# design.net
KiCad netlist of a schematic drawn in Altium Designer
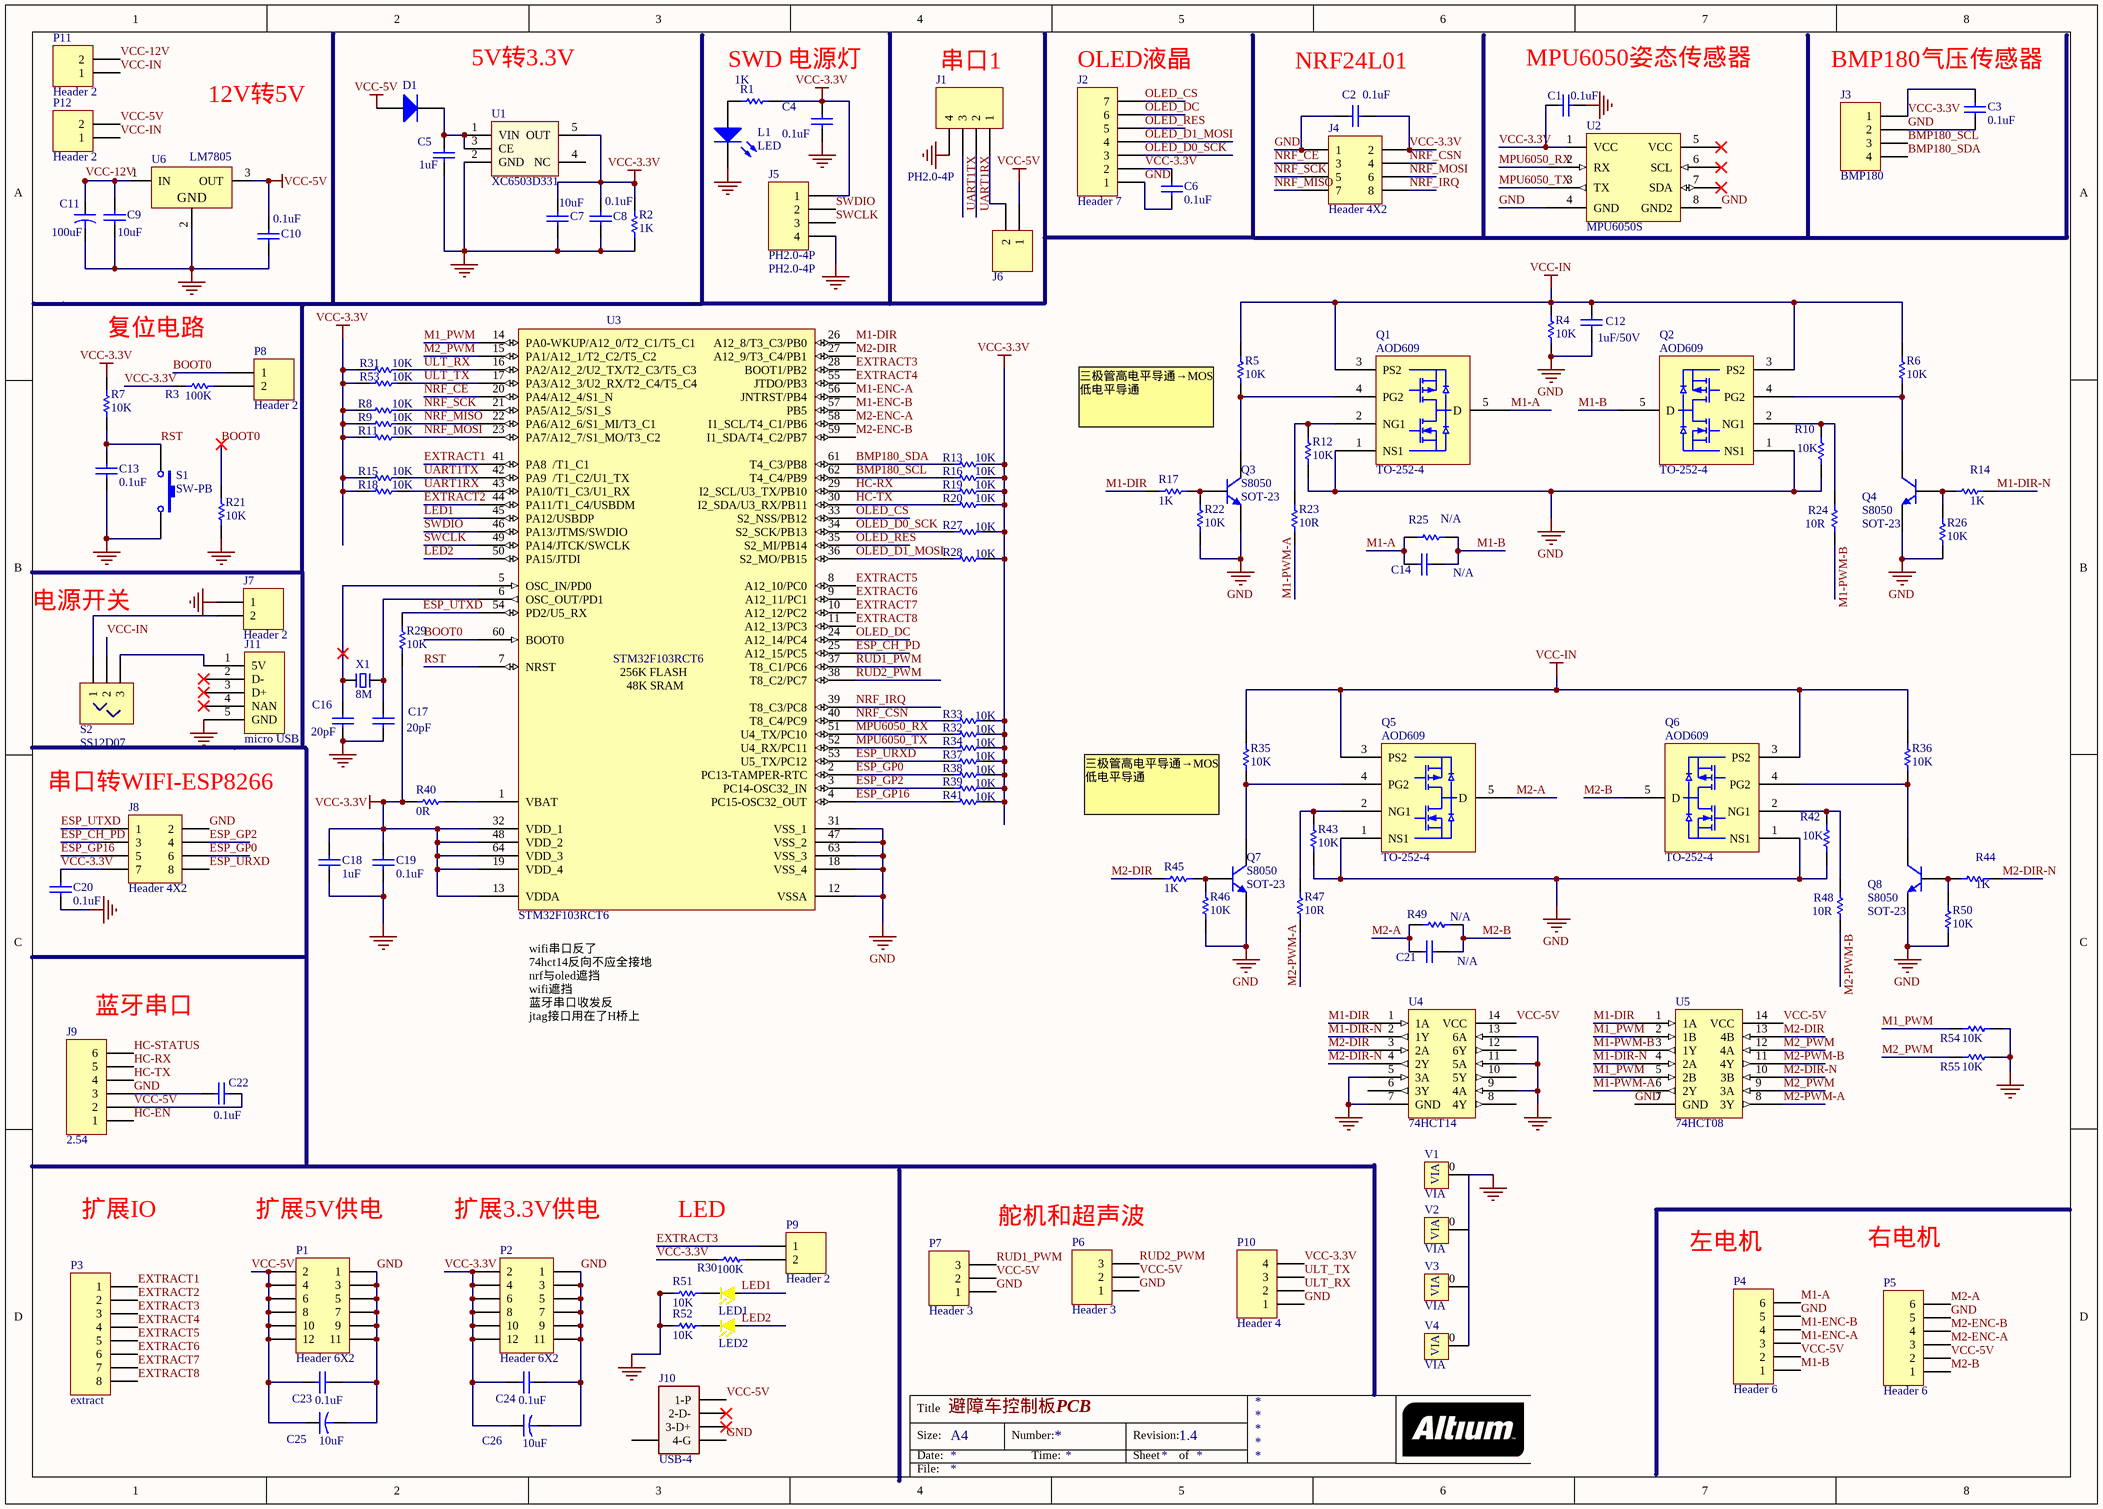
[diagram p0: 避障车控制板.SchDoc]

(export (version "E")
  (design (tool "Eeschema 10.0.6"))
  (components
    (comp (ref "C1")
      (value "0.1uF")
      (footprint "0805_N_LY")
      (description "Capacitor")
      (fields (field (name "PUBLISHER") "Altium Limited"))
      (libsource (lib "Miscellaneous Devices") (part "Cap"))
    )
    (comp (ref "C2")
      (value "0.1uF")
      (footprint "0805_N_LY")
      (description "Capacitor")
      (fields (field (name "PUBLISHER") "Altium Limited"))
      (libsource (lib "Miscellaneous Devices") (part "Cap"))
    )
    (comp (ref "C3")
      (value "0.1uF")
      (footprint "0805_N_LY")
      (description "电容0603")
      (fields (field (name "PUBLISHER") "Altium Limited"))
      (libsource (lib "Liyao原理图库") (part "Cap"))
    )
    (comp (ref "C4")
      (value "0.1uF")
      (footprint "0805_N_LY")
      (description "Capacitor")
      (fields (field (name "PUBLISHER") "Altium Limited"))
      (libsource (lib "Miscellaneous Devices") (part "Cap"))
    )
    (comp (ref "C5")
      (value "1uF")
      (footprint "0805_N_LY")
      (description "Capacitor")
      (fields (field (name "PUBLISHER") "Altium Limited"))
      (libsource (lib "Miscellaneous Devices") (part "Cap"))
    )
    (comp (ref "C6")
      (value "0.1uF")
      (footprint "0805_N_LY")
      (description "Capacitor")
      (fields (field (name "PUBLISHER") "Altium Limited"))
      (libsource (lib "Miscellaneous Devices") (part "Cap"))
    )
    (comp (ref "C7")
      (value "10uF")
      (footprint "0805_N_LY")
      (description "Capacitor")
      (fields (field (name "PUBLISHER") "Altium Limited"))
      (libsource (lib "Miscellaneous Devices") (part "Cap"))
    )
    (comp (ref "C8")
      (value "0.1uF")
      (footprint "0805_N_LY")
      (description "Capacitor")
      (fields (field (name "PUBLISHER") "Altium Limited"))
      (libsource (lib "Miscellaneous Devices") (part "Cap"))
    )
    (comp (ref "C9")
      (value "10uF")
      (footprint "0805_N_LY")
      (description "Capacitor")
      (fields (field (name "PUBLISHER") "Altium Limited"))
      (libsource (lib "Miscellaneous Devices") (part "Cap"))
    )
    (comp (ref "C10")
      (value "0.1uF")
      (footprint "0805_N_LY")
      (description "Capacitor")
      (fields (field (name "PUBLISHER") "Altium Limited"))
      (libsource (lib "Miscellaneous Devices") (part "Cap"))
    )
    (comp (ref "C11")
      (value "100uF")
      (footprint "TC6.3*7.7")
      (description "100uf/35v电解电容")
      (fields (field (name "PUBLISHER") "Altium Limited"))
      (libsource (lib "Liyao原理图库") (part "Cap100uf"))
    )
    (comp (ref "C12")
      (value "1uF/50V")
      (footprint "0805_N_LY")
      (description "Capacitor")
      (fields (field (name "PUBLISHER") "Altium Limited"))
      (libsource (lib "Miscellaneous Devices") (part "Cap"))
    )
    (comp (ref "C13")
      (value "0.1uF")
      (footprint "0805_N_LY")
      (description "Capacitor")
      (fields (field (name "PUBLISHER") "Altium Limited"))
      (libsource (lib "Miscellaneous Devices") (part "Cap"))
    )
    (comp (ref "C14")
      (value "N/A")
      (footprint "0805_N_LY")
      (description "Capacitor")
      (fields (field (name "PUBLISHER") "Altium Limited"))
      (libsource (lib "Miscellaneous Devices") (part "Cap"))
    )
    (comp (ref "C16")
      (value "20pF")
      (footprint "0805_N_LY")
      (description "Capacitor")
      (fields (field (name "PUBLISHER") "Altium Limited"))
      (libsource (lib "Miscellaneous Devices") (part "Cap"))
    )
    (comp (ref "C17")
      (value "20pF")
      (footprint "0805_N_LY")
      (description "Capacitor")
      (fields (field (name "PUBLISHER") "Altium Limited"))
      (libsource (lib "Miscellaneous Devices") (part "Cap"))
    )
    (comp (ref "C18")
      (value "1uF")
      (footprint "0805_N_LY")
      (description "Capacitor")
      (fields (field (name "PUBLISHER") "Altium Limited"))
      (libsource (lib "Miscellaneous Devices") (part "Cap"))
    )
    (comp (ref "C19")
      (value "0.1uF")
      (footprint "0805_N_LY")
      (description "Capacitor")
      (fields (field (name "PUBLISHER") "Altium Limited"))
      (libsource (lib "Miscellaneous Devices") (part "Cap"))
    )
    (comp (ref "C20")
      (value "0.1uF")
      (footprint "0805_N_LY")
      (description "Capacitor")
      (fields (field (name "PUBLISHER") "Altium Limited"))
      (libsource (lib "Miscellaneous Devices") (part "Cap"))
    )
    (comp (ref "C21")
      (value "N/A")
      (footprint "0805_N_LY")
      (description "Capacitor")
      (fields (field (name "PUBLISHER") "Altium Limited"))
      (libsource (lib "Miscellaneous Devices") (part "Cap"))
    )
    (comp (ref "C22")
      (value "0.1uF")
      (footprint "0805_N_LY")
      (description "Capacitor")
      (fields (field (name "PUBLISHER") "Altium Limited"))
      (libsource (lib "Miscellaneous Devices") (part "Cap"))
    )
    (comp (ref "C23")
      (value "0.1uF")
      (footprint "0805_N_LY")
      (description "电容0603")
      (fields (field (name "PUBLISHER") "Altium Limited"))
      (libsource (lib "Liyao原理图库") (part "Cap"))
    )
    (comp (ref "C24")
      (value "0.1uF")
      (footprint "0805_N_LY")
      (description "电容0603")
      (fields (field (name "PUBLISHER") "Altium Limited"))
      (libsource (lib "Liyao原理图库") (part "Cap"))
    )
    (comp (ref "C25")
      (value "10uF")
      (footprint "TC5*5")
      (description "10uf/35v电解电容")
      (fields (field (name "PUBLISHER") "Altium Limited"))
      (libsource (lib "Liyao原理图库") (part "Cap10uf"))
    )
    (comp (ref "C26")
      (value "10uF")
      (footprint "TC5*5")
      (description "10uf/35v电解电容")
      (fields (field (name "PUBLISHER") "Altium Limited"))
      (libsource (lib "Liyao原理图库") (part "Cap10uf"))
    )
    (comp (ref "D1")
      (value "SS14")
      (footprint "SMA")
      (description "28V 1A")
      (fields (field (name "PUBLISHER") "Altium Limited"))
      (libsource (lib "Liyao原理图库") (part "SS14"))
    )
    (comp (ref "J1")
      (value "PH2.0-4P")
      (footprint "XH2.54-4P")
      (description "插座XH2.54-4P")
      (fields (field (name "Comment") "XH2.54-4P") (field (name "PUBLISHER") "Altium Limited"))
      (libsource (lib "Liyao原理图库") (part "XH2.54-4P"))
    )
    (comp (ref "J2")
      (value "Header 7")
      (footprint "HDR1X7")
      (description "Header, 7-Pin")
      (fields (field (name "PUBLISHER") "Altium Limited"))
      (libsource (lib "Miscellaneous Connectors") (part "Header 7"))
    )
    (comp (ref "J3")
      (value "BMP180")
      (footprint "HDR1X4")
      (description "Header, 4-Pin")
      (fields (field (name "Comment") "PH2.0-4P") (field (name "PUBLISHER") "Altium Limited"))
      (libsource (lib "") (part "Header 4_1"))
    )
    (comp (ref "J4")
      (value "Header 4X2")
      (footprint "HDR2X4")
      (description "Header, 4-Pin, Dual row")
      (fields (field (name "PUBLISHER") "Altium Limited"))
      (libsource (lib "Miscellaneous Connectors") (part "Header 4X2"))
    )
    (comp (ref "J5")
      (value "PH2.0-4P")
      (footprint "PH2.0-4P")
      (description "Header, 4-Pin")
      (fields (field (name "ALTIUM_VALUE") "PH2.0-4P") (field (name "PUBLISHER") "Altium Limited"))
      (libsource (lib "") (part "Header 4_1"))
    )
    (comp (ref "J6")
      (value "XH2.54-2P")
      (footprint "CAP2.54-2P")
      (description "插座XH2.54-2P")
      (fields (field (name "PUBLISHER") "Altium Limited"))
      (libsource (lib "Liyao原理图库") (part "XH2.54-2P"))
    )
    (comp (ref "J7")
      (value "Header 2")
      (footprint "XH2.54-2P")
      (description "Header, 2-Pin")
      (fields (field (name "PUBLISHER") "Altium Limited"))
      (libsource (lib "Miscellaneous Connectors") (part "Header 2"))
    )
    (comp (ref "J8")
      (value "Header 4X2")
      (footprint "HDR2X4")
      (description "Header, 4-Pin, Dual row")
      (fields (field (name "PUBLISHER") "Altium Limited"))
      (libsource (lib "Miscellaneous Connectors") (part "Header 4X2"))
    )
    (comp (ref "J9")
      (value "2.54")
      (footprint "HDR1X6")
      (description "Header, 6-Pin")
      (fields (field (name "PUBLISHER") "Altium Limited"))
      (libsource (lib "Liyao端子库") (part "Header 6"))
    )
    (comp (ref "J10") (value "USB-4") (footprint "USB-C") (libsource (lib "Liyao原理图库") (part "USB_B")))
    (comp (ref "J11")
      (value "micro USB")
      (footprint "MICRO-USB")
      (description "micro USB母")
      (libsource (lib "Liyao原理图库") (part "micro USB"))
    )
    (comp (ref "L1") (value "LED") (footprint "0805_N_LED_LY") (libsource (lib "Sparks") (part "LED")))
    (comp (ref "LED1")
      (value "LED-Y")
      (footprint "0805_N_LED_LY")
      (description "LED黄0603")
      (libsource (lib "Liyao原理图库") (part "LED-Y"))
    )
    (comp (ref "LED2")
      (value "LED-Y")
      (footprint "0805_N_LED_LY")
      (description "LED黄0603")
      (libsource (lib "Liyao原理图库") (part "LED-Y"))
    )
    (comp (ref "P1")
      (value "Header 6X2")
      (footprint "HDR2X6")
      (description "Header, 6-Pin, Dual row")
      (fields (field (name "PUBLISHER") "Altium Limited"))
      (libsource (lib "Miscellaneous Connectors") (part "Header 6X2"))
    )
    (comp (ref "P2")
      (value "Header 6X2")
      (footprint "HDR2X6")
      (description "Header, 6-Pin, Dual row")
      (fields (field (name "PUBLISHER") "Altium Limited"))
      (libsource (lib "Miscellaneous Connectors") (part "Header 6X2"))
    )
    (comp (ref "P3")
      (value "extract")
      (footprint "HDR1X8")
      (description "Header, 8-Pin")
      (fields (field (name "PUBLISHER") "Altium Limited"))
      (libsource (lib "Miscellaneous Connectors") (part "Header 8"))
    )
    (comp (ref "P4")
      (value "Header 6")
      (footprint "PH2.0-6p")
      (description "Header, 6-Pin")
      (fields (field (name "PUBLISHER") "Altium Limited"))
      (libsource (lib "Miscellaneous Connectors") (part "Header 6"))
    )
    (comp (ref "P5")
      (value "Header 6")
      (footprint "PH2.0-6p")
      (description "Header, 6-Pin")
      (fields (field (name "PUBLISHER") "Altium Limited"))
      (libsource (lib "Miscellaneous Connectors") (part "Header 6"))
    )
    (comp (ref "P6")
      (value "Header 3")
      (footprint "HDR1X3")
      (description "Header, 3-Pin")
      (fields (field (name "PUBLISHER") "Altium Limited"))
      (libsource (lib "Miscellaneous Connectors") (part "Header 3"))
    )
    (comp (ref "P7")
      (value "Header 3")
      (footprint "HDR1X3")
      (description "Header, 3-Pin")
      (fields (field (name "PUBLISHER") "Altium Limited"))
      (libsource (lib "Miscellaneous Connectors") (part "Header 3"))
    )
    (comp (ref "P8")
      (value "Header 2")
      (footprint "HDR1X2")
      (description "Header, 2-Pin")
      (fields (field (name "PUBLISHER") "Altium Limited"))
      (libsource (lib "Liyao端子库") (part "Header 2"))
    )
    (comp (ref "P9")
      (value "Header 2")
      (footprint "HDR1X2")
      (description "Header, 2-Pin")
      (fields (field (name "PUBLISHER") "Altium Limited"))
      (libsource (lib "Liyao端子库") (part "Header 2"))
    )
    (comp (ref "P10")
      (value "Header 4")
      (footprint "HDR1X4")
      (description "Header, 4-Pin")
      (fields (field (name "PUBLISHER") "Altium Limited"))
      (libsource (lib "Miscellaneous Connectors") (part "Header 4"))
    )
    (comp (ref "P11")
      (value "Header 2")
      (footprint "CAP2.54-2P")
      (description "Header, 2-Pin")
      (fields (field (name "PUBLISHER") "Altium Limited"))
      (libsource (lib "") (part "Header 2_1"))
    )
    (comp (ref "P12")
      (value "Header 2")
      (footprint "CAP2.54-2P")
      (description "Header, 2-Pin")
      (fields (field (name "PUBLISHER") "Altium Limited"))
      (libsource (lib "") (part "Header 2_1"))
    )
    (comp (ref "Q1")
      (value "TO-252-4")
      (footprint "TO-252-4L")
      (fields (field (name "ALTIUM_VALUE") "AOD609"))
      (libsource (lib "") (part "MOS-DUAL-N/P_1"))
    )
    (comp (ref "Q2")
      (value "TO-252-4")
      (footprint "TO-252-4L")
      (fields (field (name "ALTIUM_VALUE") "AOD609"))
      (libsource (lib "CYSchlib") (part "MOS-DUAL-N/P"))
    )
    (comp (ref "Q3")
      (value "SOT-23")
      (footprint "SOT-23_N_LY")
      (description "NPN Bipolar Transistor")
      (fields (field (name "ALTIUM_VALUE") "S8050") (field (name "PUBLISHER") "Altium Limited"))
      (libsource (lib "CYSchlib") (part "NPN"))
    )
    (comp (ref "Q4")
      (value "SOT-23")
      (footprint "SOT-23_N_LY")
      (description "NPN Bipolar Transistor")
      (fields (field (name "ALTIUM_VALUE") "S8050") (field (name "PUBLISHER") "Altium Limited"))
      (libsource (lib "CYSchlib") (part "NPN"))
    )
    (comp (ref "Q5")
      (value "TO-252-4")
      (footprint "TO-252-4L")
      (fields (field (name "ALTIUM_VALUE") "AOD609"))
      (libsource (lib "") (part "MOS-DUAL-N/P_1"))
    )
    (comp (ref "Q6")
      (value "TO-252-4")
      (footprint "TO-252-4L")
      (fields (field (name "ALTIUM_VALUE") "AOD609"))
      (libsource (lib "CYSchlib") (part "MOS-DUAL-N/P"))
    )
    (comp (ref "Q7")
      (value "SOT-23")
      (footprint "SOT-23_N_LY")
      (description "NPN Bipolar Transistor")
      (fields (field (name "ALTIUM_VALUE") "S8050") (field (name "PUBLISHER") "Altium Limited"))
      (libsource (lib "CYSchlib") (part "NPN"))
    )
    (comp (ref "Q8")
      (value "SOT-23")
      (footprint "SOT-23_N_LY")
      (description "NPN Bipolar Transistor")
      (fields (field (name "ALTIUM_VALUE") "S8050") (field (name "PUBLISHER") "Altium Limited"))
      (libsource (lib "CYSchlib") (part "NPN"))
    )
    (comp (ref "R1")
      (value "1K")
      (footprint "0805_N_LY")
      (description "Resistor")
      (fields (field (name "PUBLISHER") "Altium Limited"))
      (libsource (lib "Miscellaneous Devices") (part "Res1"))
    )
    (comp (ref "R2")
      (value "1K")
      (footprint "0805_N_LY")
      (description "Resistor")
      (fields (field (name "PUBLISHER") "Altium Limited"))
      (libsource (lib "Miscellaneous Devices") (part "Res1"))
    )
    (comp (ref "R3")
      (value "100K")
      (footprint "0805_N_LY")
      (description "电阻0603")
      (fields (field (name "PUBLISHER") "Altium Limited"))
      (libsource (lib "Liyao原理图库") (part "Res"))
    )
    (comp (ref "R4")
      (value "10K")
      (footprint "0805_N_LY")
      (description "Resistor")
      (fields (field (name "PUBLISHER") "Altium Limited"))
      (libsource (lib "Miscellaneous Devices") (part "Res1"))
    )
    (comp (ref "R5")
      (value "10K")
      (footprint "0805_N_LY")
      (description "Resistor")
      (fields (field (name "PUBLISHER") "Altium Limited"))
      (libsource (lib "Miscellaneous Devices") (part "Res1"))
    )
    (comp (ref "R6")
      (value "10K")
      (footprint "0805_N_LY")
      (description "Resistor")
      (fields (field (name "PUBLISHER") "Altium Limited"))
      (libsource (lib "Miscellaneous Devices") (part "Res1"))
    )
    (comp (ref "R7")
      (value "10K")
      (footprint "0805_N_LY")
      (description "Resistor")
      (fields (field (name "PUBLISHER") "Altium Limited"))
      (libsource (lib "Miscellaneous Devices") (part "Res1"))
    )
    (comp (ref "R8")
      (value "10K")
      (footprint "0805_N_LY")
      (description "电阻0603")
      (fields (field (name "PUBLISHER") "Altium Limited"))
      (libsource (lib "Liyao原理图库") (part "Res"))
    )
    (comp (ref "R9")
      (value "10K")
      (footprint "0805_N_LY")
      (description "电阻0603")
      (fields (field (name "PUBLISHER") "Altium Limited"))
      (libsource (lib "Liyao原理图库") (part "Res"))
    )
    (comp (ref "R10")
      (value "10K")
      (footprint "0805_N_LY")
      (description "Resistor")
      (fields (field (name "PUBLISHER") "Altium Limited"))
      (libsource (lib "Miscellaneous Devices") (part "Res1"))
    )
    (comp (ref "R11")
      (value "10K")
      (footprint "0805_N_LY")
      (description "电阻0603")
      (fields (field (name "PUBLISHER") "Altium Limited"))
      (libsource (lib "Liyao原理图库") (part "Res"))
    )
    (comp (ref "R12")
      (value "10K")
      (footprint "0805_N_LY")
      (description "Resistor")
      (fields (field (name "PUBLISHER") "Altium Limited"))
      (libsource (lib "Miscellaneous Devices") (part "Res1"))
    )
    (comp (ref "R13")
      (value "10K")
      (footprint "0805_N_LY")
      (description "电阻0603")
      (fields (field (name "PUBLISHER") "Altium Limited"))
      (libsource (lib "Liyao原理图库") (part "Res"))
    )
    (comp (ref "R14")
      (value "1K")
      (footprint "0805_N_LY")
      (description "Resistor")
      (fields (field (name "PUBLISHER") "Altium Limited"))
      (libsource (lib "Miscellaneous Devices") (part "Res1"))
    )
    (comp (ref "R15")
      (value "10K")
      (footprint "0805_N_LY")
      (description "电阻0603")
      (fields (field (name "PUBLISHER") "Altium Limited"))
      (libsource (lib "Liyao原理图库") (part "Res"))
    )
    (comp (ref "R16")
      (value "10K")
      (footprint "0805_N_LY")
      (description "电阻0603")
      (fields (field (name "PUBLISHER") "Altium Limited"))
      (libsource (lib "Liyao原理图库") (part "Res"))
    )
    (comp (ref "R17")
      (value "1K")
      (footprint "0805_N_LY")
      (description "Resistor")
      (fields (field (name "PUBLISHER") "Altium Limited"))
      (libsource (lib "Miscellaneous Devices") (part "Res1"))
    )
    (comp (ref "R18")
      (value "10K")
      (footprint "0805_N_LY")
      (description "电阻0603")
      (fields (field (name "PUBLISHER") "Altium Limited"))
      (libsource (lib "Liyao原理图库") (part "Res"))
    )
    (comp (ref "R19")
      (value "10K")
      (footprint "0805_N_LY")
      (description "电阻0603")
      (fields (field (name "PUBLISHER") "Altium Limited"))
      (libsource (lib "Liyao原理图库") (part "Res"))
    )
    (comp (ref "R20")
      (value "10K")
      (footprint "0805_N_LY")
      (description "电阻0603")
      (fields (field (name "PUBLISHER") "Altium Limited"))
      (libsource (lib "Liyao原理图库") (part "Res"))
    )
    (comp (ref "R21")
      (value "10K")
      (footprint "0805_N_LY")
      (description "Resistor")
      (fields (field (name "PUBLISHER") "Altium Limited"))
      (libsource (lib "Miscellaneous Devices") (part "Res1"))
    )
    (comp (ref "R22")
      (value "10K")
      (footprint "0805_N_LY")
      (description "Resistor")
      (fields (field (name "PUBLISHER") "Altium Limited"))
      (libsource (lib "Miscellaneous Devices") (part "Res1"))
    )
    (comp (ref "R23")
      (value "10R")
      (footprint "0805_N_LY")
      (description "Resistor")
      (fields (field (name "PUBLISHER") "Altium Limited"))
      (libsource (lib "Miscellaneous Devices") (part "Res1"))
    )
    (comp (ref "R24")
      (value "10R")
      (footprint "0805_N_LY")
      (description "Resistor")
      (fields (field (name "PUBLISHER") "Altium Limited"))
      (libsource (lib "Miscellaneous Devices") (part "Res1"))
    )
    (comp (ref "R25")
      (value "N/A")
      (footprint "0805_N_LY")
      (description "Resistor")
      (fields (field (name "PUBLISHER") "Altium Limited"))
      (libsource (lib "Miscellaneous Devices") (part "Res1"))
    )
    (comp (ref "R26")
      (value "10K")
      (footprint "0805_N_LY")
      (description "Resistor")
      (fields (field (name "PUBLISHER") "Altium Limited"))
      (libsource (lib "Miscellaneous Devices") (part "Res1"))
    )
    (comp (ref "R27")
      (value "10K")
      (footprint "0805_N_LY")
      (description "电阻0603")
      (fields (field (name "PUBLISHER") "Altium Limited"))
      (libsource (lib "Liyao原理图库") (part "Res"))
    )
    (comp (ref "R28")
      (value "10K")
      (footprint "0805_N_LY")
      (description "电阻0603")
      (fields (field (name "PUBLISHER") "Altium Limited"))
      (libsource (lib "Liyao原理图库") (part "Res"))
    )
    (comp (ref "R29")
      (value "10K")
      (footprint "0805_N_LY")
      (description "电阻0603")
      (fields (field (name "PUBLISHER") "Altium Limited"))
      (libsource (lib "Liyao原理图库") (part "Res"))
    )
    (comp (ref "R30")
      (value "100K")
      (footprint "0805_N_LY")
      (description "电阻0603")
      (fields (field (name "PUBLISHER") "Altium Limited"))
      (libsource (lib "Liyao原理图库") (part "Res"))
    )
    (comp (ref "R31")
      (value "10K")
      (footprint "0805_N_LY")
      (description "电阻")
      (fields (field (name "PUBLISHER") "Altium Limited"))
      (libsource (lib "Liyao原理图库") (part "Res"))
    )
    (comp (ref "R32")
      (value "10K")
      (footprint "0805_N_LY")
      (description "电阻0603")
      (fields (field (name "PUBLISHER") "Altium Limited"))
      (libsource (lib "Liyao原理图库") (part "Res"))
    )
    (comp (ref "R33")
      (value "10K")
      (footprint "0805_N_LY")
      (description "电阻0603")
      (fields (field (name "PUBLISHER") "Altium Limited"))
      (libsource (lib "Liyao原理图库") (part "Res"))
    )
    (comp (ref "R34")
      (value "10K")
      (footprint "0805_N_LY")
      (description "电阻0603")
      (fields (field (name "PUBLISHER") "Altium Limited"))
      (libsource (lib "Liyao原理图库") (part "Res"))
    )
    (comp (ref "R35")
      (value "10K")
      (footprint "0805_N_LY")
      (description "Resistor")
      (fields (field (name "PUBLISHER") "Altium Limited"))
      (libsource (lib "Miscellaneous Devices") (part "Res1"))
    )
    (comp (ref "R36")
      (value "10K")
      (footprint "0805_N_LY")
      (description "Resistor")
      (fields (field (name "PUBLISHER") "Altium Limited"))
      (libsource (lib "Miscellaneous Devices") (part "Res1"))
    )
    (comp (ref "R37")
      (value "10K")
      (footprint "0805_N_LY")
      (description "电阻0603")
      (fields (field (name "PUBLISHER") "Altium Limited"))
      (libsource (lib "Liyao原理图库") (part "Res"))
    )
    (comp (ref "R38")
      (value "10K")
      (footprint "0805_N_LY")
      (description "电阻0603")
      (fields (field (name "PUBLISHER") "Altium Limited"))
      (libsource (lib "Liyao原理图库") (part "Res"))
    )
    (comp (ref "R39")
      (value "10K")
      (footprint "0805_N_LY")
      (description "电阻0603")
      (fields (field (name "PUBLISHER") "Altium Limited"))
      (libsource (lib "Liyao原理图库") (part "Res"))
    )
    (comp (ref "R40")
      (value "0R")
      (footprint "0805_N_LY")
      (description "Resistor")
      (fields (field (name "PUBLISHER") "Altium Limited"))
      (libsource (lib "Miscellaneous Devices") (part "Res1"))
    )
    (comp (ref "R41")
      (value "10K")
      (footprint "0805_N_LY")
      (description "电阻0603")
      (fields (field (name "PUBLISHER") "Altium Limited"))
      (libsource (lib "Liyao原理图库") (part "Res"))
    )
    (comp (ref "R42")
      (value "10K")
      (footprint "0805_N_LY")
      (description "Resistor")
      (fields (field (name "PUBLISHER") "Altium Limited"))
      (libsource (lib "Miscellaneous Devices") (part "Res1"))
    )
    (comp (ref "R43")
      (value "10K")
      (footprint "0805_N_LY")
      (description "Resistor")
      (fields (field (name "PUBLISHER") "Altium Limited"))
      (libsource (lib "Miscellaneous Devices") (part "Res1"))
    )
    (comp (ref "R44")
      (value "1K")
      (footprint "0805_N_LY")
      (description "Resistor")
      (fields (field (name "PUBLISHER") "Altium Limited"))
      (libsource (lib "Miscellaneous Devices") (part "Res1"))
    )
    (comp (ref "R45")
      (value "1K")
      (footprint "0805_N_LY")
      (description "Resistor")
      (fields (field (name "PUBLISHER") "Altium Limited"))
      (libsource (lib "Miscellaneous Devices") (part "Res1"))
    )
    (comp (ref "R46")
      (value "10K")
      (footprint "0805_N_LY")
      (description "Resistor")
      (fields (field (name "PUBLISHER") "Altium Limited"))
      (libsource (lib "Miscellaneous Devices") (part "Res1"))
    )
    (comp (ref "R47")
      (value "10R")
      (footprint "0805_N_LY")
      (description "Resistor")
      (fields (field (name "PUBLISHER") "Altium Limited"))
      (libsource (lib "Miscellaneous Devices") (part "Res1"))
    )
    (comp (ref "R48")
      (value "10R")
      (footprint "0805_N_LY")
      (description "Resistor")
      (fields (field (name "PUBLISHER") "Altium Limited"))
      (libsource (lib "Miscellaneous Devices") (part "Res1"))
    )
    (comp (ref "R49")
      (value "N/A")
      (footprint "0805_N_LY")
      (description "Resistor")
      (fields (field (name "PUBLISHER") "Altium Limited"))
      (libsource (lib "Miscellaneous Devices") (part "Res1"))
    )
    (comp (ref "R50")
      (value "10K")
      (footprint "0805_N_LY")
      (description "Resistor")
      (fields (field (name "PUBLISHER") "Altium Limited"))
      (libsource (lib "Miscellaneous Devices") (part "Res1"))
    )
    (comp (ref "R51")
      (value "10K")
      (footprint "0805_N_LY")
      (description "电阻0603")
      (fields (field (name "PUBLISHER") "Altium Limited"))
      (libsource (lib "Liyao原理图库") (part "Res"))
    )
    (comp (ref "R52")
      (value "10K")
      (footprint "0805_N_LY")
      (description "电阻0603")
      (fields (field (name "PUBLISHER") "Altium Limited"))
      (libsource (lib "Liyao原理图库") (part "Res"))
    )
    (comp (ref "R53")
      (value "10K")
      (footprint "0805_N_LY")
      (description "电阻")
      (fields (field (name "PUBLISHER") "Altium Limited"))
      (libsource (lib "Liyao原理图库") (part "Res"))
    )
    (comp (ref "R54")
      (value "10K")
      (footprint "0805_N_LY")
      (description "电阻")
      (fields (field (name "PUBLISHER") "Altium Limited"))
      (libsource (lib "Liyao原理图库") (part "Res"))
    )
    (comp (ref "R55")
      (value "10K")
      (footprint "0805_N_LY")
      (description "电阻")
      (fields (field (name "PUBLISHER") "Altium Limited"))
      (libsource (lib "Liyao原理图库") (part "Res"))
    )
    (comp (ref "S1")
      (value "SW-PB")
      (footprint "SW-KEY")
      (description "Switch")
      (fields (field (name "PUBLISHER") "Altium Limited"))
      (libsource (lib "Miscellaneous Devices") (part "SW-PB"))
    )
    (comp (ref "S2") (value "SS12D07") (footprint "SS-12D07") (libsource (lib "Liyao原理图库") (part "SS12D07")))
    (comp (ref "U1")
      (value "XC6503D331")
      (footprint "SOT23-5")
      (libsource (lib "CYSchlib") (part "XC6503Dxxx"))
    )
    (comp (ref "U2")
      (value "MPU6050S")
      (footprint "MPU6050S")
      (libsource (lib "Liyao原理图库") (part "MPU6050S"))
    )
    (comp (ref "U3")
      (value "STM32F103RCT6")
      (footprint "LQFP64_N")
      (description "256K Flash 48K RAM")
      (fields (field (name "PUBLISHER") "Altium Limited"))
      (libsource (lib "Liyao原理图库") (part "STM32F103RCT6"))
    )
    (comp (ref "U4")
      (value "74HCT14")
      (footprint "SO-14")
      (description "反向输出 AL-YH,AH-YL")
      (libsource (lib "Liyao原理图库") (part "74HCT14"))
    )
    (comp (ref "U5")
      (value "74HCT08")
      (footprint "SO-14")
      (description "与门AH&&BH?YH:YL")
      (libsource (lib "Liyao原理图库") (part "74HCT08"))
    )
    (comp (ref "U6")
      (value "LM7805")
      (footprint "TO-220")
      (description "三端稳压，05代表电压")
      (libsource (lib "Liyao原理图库") (part "LM7805"))
    )
    (comp (ref "V1")
      (value "VIA")
      (footprint "SH3.3")
      (description "焊盘")
      (libsource (lib "Liyao原理图库") (part "VIA"))
    )
    (comp (ref "V2")
      (value "VIA")
      (footprint "SH3.3")
      (description "焊盘")
      (libsource (lib "Liyao原理图库") (part "VIA"))
    )
    (comp (ref "V3")
      (value "VIA")
      (footprint "SH3.3")
      (description "焊盘")
      (libsource (lib "Liyao原理图库") (part "VIA"))
    )
    (comp (ref "V4")
      (value "VIA")
      (footprint "SH3.3")
      (description "焊盘")
      (libsource (lib "Liyao原理图库") (part "VIA"))
    )
    (comp (ref "X1") (value "8M") (footprint "HC-49SMD") (libsource (lib "CYSchlib") (part "XTAL")))
  )
  (nets
    (net (code "1") (name "/BMP180_SCL") (class "Default")
      (node (ref "J3") (pin "3") (pinfunction "3_3") (pintype "passive"))
      (node (ref "R16") (pin "1") (pinfunction "1_1") (pintype "passive"))
      (node (ref "U3") (pin "62") (pinfunction "T4_C4/PB9_62") (pintype "bidirectional"))
    )
    (net (code "2") (name "/BMP180_SDA") (class "Default")
      (node (ref "J3") (pin "4") (pinfunction "4_4") (pintype "passive"))
      (node (ref "R13") (pin "1") (pinfunction "1_1") (pintype "passive"))
      (node (ref "U3") (pin "61") (pinfunction "T4_C3/PB8_61") (pintype "bidirectional"))
    )
    (net (code "3") (name "/BOOT0") (class "Default")
      (node (ref "P8") (pin "1") (pinfunction "1_1") (pintype "passive"))
      (node (ref "R21") (pin "1") (pinfunction "1_1") (pintype "passive"))
      (node (ref "U3") (pin "60") (pinfunction "BOOT0_60") (pintype "input"))
    )
    (net (code "4") (name "/ESP_CH_PD") (class "Default")
      (node (ref "J8") (pin "3") (pinfunction "3_3") (pintype "passive"))
      (node (ref "U3") (pin "25") (pinfunction "A12_15/PC5_25") (pintype "bidirectional"))
    )
    (net (code "5") (name "/ESP_GP0") (class "Default")
      (node (ref "J8") (pin "6") (pinfunction "6_6") (pintype "passive"))
      (node (ref "R38") (pin "1") (pinfunction "1_1") (pintype "passive"))
      (node (ref "U3") (pin "2") (pinfunction "PC13-TAMPER-RTC_2") (pintype "bidirectional"))
    )
    (net (code "6") (name "/ESP_GP2") (class "Default")
      (node (ref "J8") (pin "4") (pinfunction "4_4") (pintype "passive"))
      (node (ref "R39") (pin "1") (pinfunction "1_1") (pintype "passive"))
      (node (ref "U3") (pin "3") (pinfunction "PC14-OSC32_IN_3") (pintype "bidirectional"))
    )
    (net (code "7") (name "/ESP_GP16") (class "Default")
      (node (ref "J8") (pin "5") (pinfunction "5_5") (pintype "passive"))
      (node (ref "R41") (pin "1") (pinfunction "1_1") (pintype "passive"))
      (node (ref "U3") (pin "4") (pinfunction "PC15-OSC32_OUT_4") (pintype "bidirectional"))
    )
    (net (code "8") (name "/ESP_URXD") (class "Default")
      (node (ref "J8") (pin "8") (pinfunction "8_8") (pintype "passive"))
      (node (ref "R37") (pin "1") (pinfunction "1_1") (pintype "passive"))
      (node (ref "U3") (pin "53") (pinfunction "U5_TX/PC12_53") (pintype "bidirectional"))
    )
    (net (code "9") (name "/ESP_UTXD") (class "Default")
      (node (ref "J8") (pin "1") (pinfunction "1_1") (pintype "passive"))
      (node (ref "R29") (pin "2") (pinfunction "2_2") (pintype "passive"))
      (node (ref "U3") (pin "54") (pinfunction "PD2/U5_RX_54") (pintype "bidirectional"))
    )
    (net (code "10") (name "/EXTRACT1") (class "Default")
      (node (ref "P3") (pin "1") (pinfunction "1_1") (pintype "passive"))
      (node (ref "U3") (pin "41") (pinfunction "PA8__/T1_C1_41") (pintype "bidirectional"))
    )
    (net (code "11") (name "/EXTRACT2") (class "Default")
      (node (ref "P3") (pin "2") (pinfunction "2_2") (pintype "passive"))
      (node (ref "U3") (pin "44") (pinfunction "PA11/T1_C4/USBDM_44") (pintype "bidirectional"))
    )
    (net (code "12") (name "/EXTRACT3") (class "Default")
      (node (ref "P3") (pin "3") (pinfunction "3_3") (pintype "passive"))
      (node (ref "P9") (pin "1") (pinfunction "1_1") (pintype "passive"))
      (node (ref "U3") (pin "28") (pinfunction "BOOT1/PB2_28") (pintype "bidirectional"))
    )
    (net (code "13") (name "/EXTRACT4") (class "Default")
      (node (ref "P3") (pin "4") (pinfunction "4_4") (pintype "passive"))
      (node (ref "U3") (pin "55") (pinfunction "JTDO/PB3_55") (pintype "bidirectional"))
    )
    (net (code "14") (name "/EXTRACT5") (class "Default")
      (node (ref "P3") (pin "5") (pinfunction "5_5") (pintype "passive"))
      (node (ref "U3") (pin "8") (pinfunction "A12_10/PC0_8") (pintype "bidirectional"))
    )
    (net (code "15") (name "/EXTRACT6") (class "Default")
      (node (ref "P3") (pin "6") (pinfunction "6_6") (pintype "passive"))
      (node (ref "U3") (pin "9") (pinfunction "A12_11/PC1_9") (pintype "bidirectional"))
    )
    (net (code "16") (name "/EXTRACT7") (class "Default")
      (node (ref "P3") (pin "7") (pinfunction "7_7") (pintype "passive"))
      (node (ref "U3") (pin "10") (pinfunction "A12_12/PC2_10") (pintype "bidirectional"))
    )
    (net (code "17") (name "/EXTRACT8") (class "Default")
      (node (ref "P3") (pin "8") (pinfunction "8_8") (pintype "passive"))
      (node (ref "U3") (pin "11") (pinfunction "A12_13/PC3_11") (pintype "bidirectional"))
    )
    (net (code "18") (name "/HC-EN") (class "Default")
      (node (ref "J9") (pin "1") (pinfunction "1_1") (pintype "passive"))
    )
    (net (code "19") (name "/HC-RX") (class "Default")
      (node (ref "J9") (pin "5") (pinfunction "5_5") (pintype "passive"))
      (node (ref "R19") (pin "1") (pinfunction "1_1") (pintype "passive"))
      (node (ref "U3") (pin "29") (pinfunction "I2_SCL/U3_TX/PB10_29") (pintype "bidirectional"))
    )
    (net (code "20") (name "/HC-STATUS") (class "Default")
      (node (ref "J9") (pin "6") (pinfunction "6_6") (pintype "passive"))
    )
    (net (code "21") (name "/HC-TX") (class "Default")
      (node (ref "J9") (pin "4") (pinfunction "4_4") (pintype "passive"))
      (node (ref "R20") (pin "1") (pinfunction "1_1") (pintype "passive"))
      (node (ref "U3") (pin "30") (pinfunction "I2_SDA/U3_RX/PB11_30") (pintype "bidirectional"))
    )
    (net (code "22") (name "/LED1") (class "Default")
      (node (ref "LED1") (pin "1") (pinfunction "1_1") (pintype "passive"))
      (node (ref "U3") (pin "45") (pinfunction "PA12/USBDP_45") (pintype "bidirectional"))
    )
    (net (code "23") (name "/LED2") (class "Default")
      (node (ref "LED2") (pin "1") (pinfunction "1_1") (pintype "passive"))
      (node (ref "U3") (pin "50") (pinfunction "PA15/JTDI_50") (pintype "bidirectional"))
    )
    (net (code "24") (name "/M1-A") (class "Default")
      (node (ref "C14") (pin "2") (pinfunction "2_2") (pintype "passive"))
      (node (ref "P4") (pin "6") (pinfunction "6_6") (pintype "passive"))
      (node (ref "Q1") (pin "5") (pinfunction "D_5") (pintype "passive"))
      (node (ref "R25") (pin "2") (pinfunction "2_2") (pintype "passive"))
    )
    (net (code "25") (name "/M1-B") (class "Default")
      (node (ref "C14") (pin "1") (pinfunction "1_1") (pintype "passive"))
      (node (ref "P4") (pin "1") (pinfunction "1_1") (pintype "passive"))
      (node (ref "Q2") (pin "5") (pinfunction "D_5") (pintype "passive"))
      (node (ref "R25") (pin "1") (pinfunction "1_1") (pintype "passive"))
    )
    (net (code "26") (name "/M1-DIR") (class "Default")
      (node (ref "R17") (pin "2") (pinfunction "2_2") (pintype "passive"))
      (node (ref "U3") (pin "26") (pinfunction "A12_8/T3_C3/PB0_26") (pintype "bidirectional"))
      (node (ref "U4") (pin "1") (pinfunction "1A_1") (pintype "input"))
      (node (ref "U5") (pin "1") (pinfunction "1A_1") (pintype "input"))
    )
    (net (code "27") (name "/M1-DIR-N") (class "Default")
      (node (ref "R14") (pin "1") (pinfunction "1_1") (pintype "passive"))
      (node (ref "U4") (pin "2") (pinfunction "1Y_2") (pintype "output"))
      (node (ref "U5") (pin "4") (pinfunction "2A_4") (pintype "input"))
    )
    (net (code "28") (name "/M1-ENC-A") (class "Default")
      (node (ref "P4") (pin "3") (pinfunction "3_3") (pintype "passive"))
      (node (ref "U3") (pin "56") (pinfunction "JNTRST/PB4_56") (pintype "bidirectional"))
    )
    (net (code "29") (name "/M1-ENC-B") (class "Default")
      (node (ref "P4") (pin "4") (pinfunction "4_4") (pintype "passive"))
      (node (ref "U3") (pin "57") (pinfunction "PB5_57") (pintype "bidirectional"))
    )
    (net (code "30") (name "/M1-PWM-A") (class "Default")
      (node (ref "R23") (pin "2") (pinfunction "2_2") (pintype "passive"))
      (node (ref "U5") (pin "6") (pinfunction "2Y_6") (pintype "output"))
    )
    (net (code "31") (name "/M1-PWM-B") (class "Default")
      (node (ref "R24") (pin "2") (pinfunction "2_2") (pintype "passive"))
      (node (ref "U5") (pin "3") (pinfunction "1Y_3") (pintype "output"))
    )
    (net (code "32") (name "/M1_PWM") (class "Default")
      (node (ref "R54") (pin "1") (pinfunction "1_1") (pintype "passive"))
      (node (ref "U3") (pin "14") (pinfunction "PA0-WKUP/A12_0/T2_C1/T5_C1_14") (pintype "bidirectional"))
      (node (ref "U5") (pin "2") (pinfunction "1B_2") (pintype "input"))
      (node (ref "U5") (pin "5") (pinfunction "2B_5") (pintype "input"))
    )
    (net (code "33") (name "/M2-A") (class "Default")
      (node (ref "C21") (pin "2") (pinfunction "2_2") (pintype "passive"))
      (node (ref "P5") (pin "6") (pinfunction "6_6") (pintype "passive"))
      (node (ref "Q5") (pin "5") (pinfunction "D_5") (pintype "passive"))
      (node (ref "R49") (pin "2") (pinfunction "2_2") (pintype "passive"))
    )
    (net (code "34") (name "/M2-B") (class "Default")
      (node (ref "C21") (pin "1") (pinfunction "1_1") (pintype "passive"))
      (node (ref "P5") (pin "1") (pinfunction "1_1") (pintype "passive"))
      (node (ref "Q6") (pin "5") (pinfunction "D_5") (pintype "passive"))
      (node (ref "R49") (pin "1") (pinfunction "1_1") (pintype "passive"))
    )
    (net (code "35") (name "/M2-DIR") (class "Default")
      (node (ref "R45") (pin "2") (pinfunction "2_2") (pintype "passive"))
      (node (ref "U3") (pin "27") (pinfunction "A12_9/T3_C4/PB1_27") (pintype "bidirectional"))
      (node (ref "U4") (pin "3") (pinfunction "2A_3") (pintype "input"))
      (node (ref "U5") (pin "13") (pinfunction "4B_13") (pintype "input"))
    )
    (net (code "36") (name "/M2-DIR-N") (class "Default")
      (node (ref "R44") (pin "1") (pinfunction "1_1") (pintype "passive"))
      (node (ref "U4") (pin "4") (pinfunction "2Y_4") (pintype "output"))
      (node (ref "U5") (pin "10") (pinfunction "3B_10") (pintype "input"))
    )
    (net (code "37") (name "/M2-ENC-A") (class "Default")
      (node (ref "P5") (pin "3") (pinfunction "3_3") (pintype "passive"))
      (node (ref "U3") (pin "58") (pinfunction "I1_SCL/T4_C1/PB6_58") (pintype "bidirectional"))
    )
    (net (code "38") (name "/M2-ENC-B") (class "Default")
      (node (ref "P5") (pin "4") (pinfunction "4_4") (pintype "passive"))
      (node (ref "U3") (pin "59") (pinfunction "I1_SDA/T4_C2/PB7_59") (pintype "bidirectional"))
    )
    (net (code "39") (name "/M2-PWM-A") (class "Default")
      (node (ref "R47") (pin "2") (pinfunction "2_2") (pintype "passive"))
      (node (ref "U5") (pin "8") (pinfunction "3Y_8") (pintype "output"))
    )
    (net (code "40") (name "/M2-PWM-B") (class "Default")
      (node (ref "R48") (pin "2") (pinfunction "2_2") (pintype "passive"))
      (node (ref "U5") (pin "11") (pinfunction "4Y_11") (pintype "output"))
    )
    (net (code "41") (name "/M2_PWM") (class "Default")
      (node (ref "R55") (pin "1") (pinfunction "1_1") (pintype "passive"))
      (node (ref "U3") (pin "15") (pinfunction "PA1/A12_1/T2_C2/T5_C2_15") (pintype "bidirectional"))
      (node (ref "U5") (pin "12") (pinfunction "4A_12") (pintype "input"))
      (node (ref "U5") (pin "9") (pinfunction "3A_9") (pintype "input"))
    )
    (net (code "42") (name "/MPU6050_RX") (class "Default")
      (node (ref "R32") (pin "1") (pinfunction "1_1") (pintype "passive"))
      (node (ref "U2") (pin "2") (pinfunction "RX_2") (pintype "input"))
      (node (ref "U3") (pin "51") (pinfunction "U4_TX/PC10_51") (pintype "bidirectional"))
    )
    (net (code "43") (name "/MPU6050_TX") (class "Default")
      (node (ref "R34") (pin "1") (pinfunction "1_1") (pintype "passive"))
      (node (ref "U2") (pin "3") (pinfunction "TX_3") (pintype "output"))
      (node (ref "U3") (pin "52") (pinfunction "U4_RX/PC11_52") (pintype "bidirectional"))
    )
    (net (code "44") (name "/NRF_CE") (class "Default")
      (node (ref "J4") (pin "3") (pinfunction "3_3") (pintype "passive"))
      (node (ref "U3") (pin "20") (pinfunction "PA4/A12_4/S1_N_20") (pintype "bidirectional"))
    )
    (net (code "45") (name "/NRF_CSN") (class "Default")
      (node (ref "J4") (pin "4") (pinfunction "4_4") (pintype "passive"))
      (node (ref "R33") (pin "1") (pinfunction "1_1") (pintype "passive"))
      (node (ref "U3") (pin "40") (pinfunction "T8_C4/PC9_40") (pintype "bidirectional"))
    )
    (net (code "46") (name "/NRF_IRQ") (class "Default")
      (node (ref "J4") (pin "8") (pinfunction "8_8") (pintype "passive"))
      (node (ref "U3") (pin "39") (pinfunction "T8_C3/PC8_39") (pintype "bidirectional"))
    )
    (net (code "47") (name "/NRF_MISO") (class "Default")
      (node (ref "J4") (pin "7") (pinfunction "7_7") (pintype "passive"))
      (node (ref "R9") (pin "2") (pinfunction "2_2") (pintype "passive"))
      (node (ref "U3") (pin "22") (pinfunction "PA6/A12_6/S1_MI/T3_C1_22") (pintype "bidirectional"))
    )
    (net (code "48") (name "/NRF_MOSI") (class "Default")
      (node (ref "J4") (pin "6") (pinfunction "6_6") (pintype "passive"))
      (node (ref "R11") (pin "2") (pinfunction "2_2") (pintype "passive"))
      (node (ref "U3") (pin "23") (pinfunction "PA7/A12_7/S1_MO/T3_C2_23") (pintype "bidirectional"))
    )
    (net (code "49") (name "/NRF_SCK") (class "Default")
      (node (ref "J4") (pin "5") (pinfunction "5_5") (pintype "passive"))
      (node (ref "R8") (pin "2") (pinfunction "2_2") (pintype "passive"))
      (node (ref "U3") (pin "21") (pinfunction "PA5/A12_5/S1_S_21") (pintype "bidirectional"))
    )
    (net (code "50") (name "/OLED_CS") (class "Default")
      (node (ref "J2") (pin "7") (pinfunction "7_7") (pintype "passive"))
      (node (ref "U3") (pin "33") (pinfunction "S2_NSS/PB12_33") (pintype "bidirectional"))
    )
    (net (code "51") (name "/OLED_D0_SCK") (class "Default")
      (node (ref "J2") (pin "3") (pinfunction "3_3") (pintype "passive"))
      (node (ref "R27") (pin "1") (pinfunction "1_1") (pintype "passive"))
      (node (ref "U3") (pin "34") (pinfunction "S2_SCK/PB13_34") (pintype "bidirectional"))
    )
    (net (code "52") (name "/OLED_D1_MOSI") (class "Default")
      (node (ref "J2") (pin "4") (pinfunction "4_4") (pintype "passive"))
      (node (ref "R28") (pin "1") (pinfunction "1_1") (pintype "passive"))
      (node (ref "U3") (pin "36") (pinfunction "S2_MO/PB15_36") (pintype "bidirectional"))
    )
    (net (code "53") (name "/OLED_DC") (class "Default")
      (node (ref "J2") (pin "6") (pinfunction "6_6") (pintype "passive"))
      (node (ref "U3") (pin "24") (pinfunction "A12_14/PC4_24") (pintype "bidirectional"))
    )
    (net (code "54") (name "/OLED_RES") (class "Default")
      (node (ref "J2") (pin "5") (pinfunction "5_5") (pintype "passive"))
      (node (ref "U3") (pin "35") (pinfunction "S2_MI/PB14_35") (pintype "bidirectional"))
    )
    (net (code "55") (name "/RST") (class "Default")
      (node (ref "C13") (pin "1") (pinfunction "1_1") (pintype "passive"))
      (node (ref "R7") (pin "2") (pinfunction "2_2") (pintype "passive"))
      (node (ref "S1") (pin "1") (pinfunction "1_1") (pintype "passive"))
      (node (ref "U3") (pin "7") (pinfunction "NRST_7") (pintype "bidirectional"))
    )
    (net (code "56") (name "/RUD1_PWM") (class "Default")
      (node (ref "P7") (pin "3") (pinfunction "3_3") (pintype "passive"))
      (node (ref "U3") (pin "37") (pinfunction "T8_C1/PC6_37") (pintype "bidirectional"))
    )
    (net (code "57") (name "/RUD2_PWM") (class "Default")
      (node (ref "P6") (pin "3") (pinfunction "3_3") (pintype "passive"))
      (node (ref "U3") (pin "38") (pinfunction "T8_C2/PC7_38") (pintype "bidirectional"))
    )
    (net (code "58") (name "/SWCLK") (class "Default")
      (node (ref "J5") (pin "3") (pinfunction "3_3") (pintype "passive"))
      (node (ref "U3") (pin "49") (pinfunction "PA14/JTCK/SWCLK_49") (pintype "bidirectional"))
    )
    (net (code "59") (name "/SWDIO") (class "Default")
      (node (ref "J5") (pin "2") (pinfunction "2_2") (pintype "passive"))
      (node (ref "U3") (pin "46") (pinfunction "PA13/JTMS/SWDIO_46") (pintype "bidirectional"))
    )
    (net (code "60") (name "/UART1RX") (class "Default")
      (node (ref "J1") (pin "2") (pinfunction "2_2") (pintype "passive"))
      (node (ref "R18") (pin "2") (pinfunction "2_2") (pintype "passive"))
      (node (ref "U3") (pin "43") (pinfunction "PA10/T1_C3/U1_RX_43") (pintype "bidirectional"))
    )
    (net (code "61") (name "/UART1TX") (class "Default")
      (node (ref "J1") (pin "3") (pinfunction "3_3") (pintype "passive"))
      (node (ref "R15") (pin "2") (pinfunction "2_2") (pintype "passive"))
      (node (ref "U3") (pin "42") (pinfunction "PA9__/T1_C2/U1_TX_42") (pintype "bidirectional"))
    )
    (net (code "62") (name "/ULT_RX") (class "Default")
      (node (ref "P10") (pin "2") (pinfunction "2_2") (pintype "passive"))
      (node (ref "R31") (pin "2") (pinfunction "2_2") (pintype "passive"))
      (node (ref "U3") (pin "16") (pinfunction "PA2/A12_2/U2_TX/T2_C3/T5_C3_16") (pintype "bidirectional"))
    )
    (net (code "63") (name "/ULT_TX") (class "Default")
      (node (ref "P10") (pin "3") (pinfunction "3_3") (pintype "passive"))
      (node (ref "R53") (pin "2") (pinfunction "2_2") (pintype "passive"))
      (node (ref "U3") (pin "17") (pinfunction "PA3/A12_3/U2_RX/T2_C4/T5_C4_17") (pintype "bidirectional"))
    )
    (net (code "64") (name "/VCC-12V") (class "Default")
      (node (ref "C11") (pin "1") (pinfunction "1_1") (pintype "passive"))
      (node (ref "C9") (pin "1") (pinfunction "1_1") (pintype "passive"))
      (node (ref "P11") (pin "2") (pinfunction "2_2") (pintype "passive"))
      (node (ref "U6") (pin "1") (pinfunction "IN_1") (pintype "passive"))
    )
    (net (code "65") (name "GND") (class "Default")
      (node (ref "C1") (pin "2") (pinfunction "2_2") (pintype "passive"))
      (node (ref "C10") (pin "2") (pinfunction "2_2") (pintype "passive"))
      (node (ref "C11") (pin "2") (pinfunction "2_2") (pintype "passive"))
      (node (ref "C12") (pin "2") (pinfunction "2_2") (pintype "passive"))
      (node (ref "C13") (pin "2") (pinfunction "2_2") (pintype "passive"))
      (node (ref "C16") (pin "1") (pinfunction "1_1") (pintype "passive"))
      (node (ref "C17") (pin "1") (pinfunction "1_1") (pintype "passive"))
      (node (ref "C18") (pin "1") (pinfunction "1_1") (pintype "passive"))
      (node (ref "C19") (pin "1") (pinfunction "1_1") (pintype "passive"))
      (node (ref "C2") (pin "2") (pinfunction "2_2") (pintype "passive"))
      (node (ref "C20") (pin "1") (pinfunction "1_1") (pintype "passive"))
      (node (ref "C22") (pin "1") (pinfunction "1_1") (pintype "passive"))
      (node (ref "C23") (pin "2") (pinfunction "2_2") (pintype "passive"))
      (node (ref "C24") (pin "2") (pinfunction "2_2") (pintype "passive"))
      (node (ref "C25") (pin "2") (pinfunction "2_2") (pintype "passive"))
      (node (ref "C26") (pin "2") (pinfunction "2_2") (pintype "passive"))
      (node (ref "C3") (pin "1") (pinfunction "1_1") (pintype "passive"))
      (node (ref "C4") (pin "2") (pinfunction "2_2") (pintype "passive"))
      (node (ref "C5") (pin "1") (pinfunction "1_1") (pintype "passive"))
      (node (ref "C6") (pin "2") (pinfunction "2_2") (pintype "passive"))
      (node (ref "C7") (pin "2") (pinfunction "2_2") (pintype "passive"))
      (node (ref "C8") (pin "2") (pinfunction "2_2") (pintype "passive"))
      (node (ref "C9") (pin "2") (pinfunction "2_2") (pintype "passive"))
      (node (ref "J1") (pin "4") (pinfunction "4_4") (pintype "passive"))
      (node (ref "J10") (pin "4") (pinfunction "4-G_4") (pintype "passive"))
      (node (ref "J11") (pin "5") (pinfunction "GND_5") (pintype "passive"))
      (node (ref "J2") (pin "1") (pinfunction "1_1") (pintype "passive"))
      (node (ref "J3") (pin "2") (pinfunction "2_2") (pintype "passive"))
      (node (ref "J4") (pin "1") (pinfunction "1_1") (pintype "passive"))
      (node (ref "J5") (pin "4") (pinfunction "4_4") (pintype "passive"))
      (node (ref "J7") (pin "1") (pinfunction "1_1") (pintype "passive"))
      (node (ref "J8") (pin "2") (pinfunction "2_2") (pintype "passive"))
      (node (ref "J9") (pin "3") (pinfunction "3_3") (pintype "passive"))
      (node (ref "L1") (pin "2") (pinfunction "K_2") (pintype "passive"))
      (node (ref "P1") (pin "1") (pinfunction "1_1") (pintype "passive"))
      (node (ref "P1") (pin "11") (pinfunction "11_11") (pintype "passive"))
      (node (ref "P1") (pin "3") (pinfunction "3_3") (pintype "passive"))
      (node (ref "P1") (pin "5") (pinfunction "5_5") (pintype "passive"))
      (node (ref "P1") (pin "7") (pinfunction "7_7") (pintype "passive"))
      (node (ref "P1") (pin "9") (pinfunction "9_9") (pintype "passive"))
      (node (ref "P10") (pin "1") (pinfunction "1_1") (pintype "passive"))
      (node (ref "P2") (pin "1") (pinfunction "1_1") (pintype "passive"))
      (node (ref "P2") (pin "11") (pinfunction "11_11") (pintype "passive"))
      (node (ref "P2") (pin "3") (pinfunction "3_3") (pintype "passive"))
      (node (ref "P2") (pin "5") (pinfunction "5_5") (pintype "passive"))
      (node (ref "P2") (pin "7") (pinfunction "7_7") (pintype "passive"))
      (node (ref "P2") (pin "9") (pinfunction "9_9") (pintype "passive"))
      (node (ref "P4") (pin "5") (pinfunction "5_5") (pintype "passive"))
      (node (ref "P5") (pin "5") (pinfunction "5_5") (pintype "passive"))
      (node (ref "P6") (pin "1") (pinfunction "1_1") (pintype "passive"))
      (node (ref "P7") (pin "1") (pinfunction "1_1") (pintype "passive"))
      (node (ref "Q1") (pin "1") (pinfunction "NS1_1") (pintype "passive"))
      (node (ref "Q2") (pin "1") (pinfunction "NS1_1") (pintype "passive"))
      (node (ref "Q3") (pin "2") (pinfunction "E_2") (pintype "passive"))
      (node (ref "Q4") (pin "2") (pinfunction "E_2") (pintype "passive"))
      (node (ref "Q5") (pin "1") (pinfunction "NS1_1") (pintype "passive"))
      (node (ref "Q6") (pin "1") (pinfunction "NS1_1") (pintype "passive"))
      (node (ref "Q7") (pin "2") (pinfunction "E_2") (pintype "passive"))
      (node (ref "Q8") (pin "2") (pinfunction "E_2") (pintype "passive"))
      (node (ref "R10") (pin "2") (pinfunction "2_2") (pintype "passive"))
      (node (ref "R12") (pin "2") (pinfunction "2_2") (pintype "passive"))
      (node (ref "R2") (pin "1") (pinfunction "1_1") (pintype "passive"))
      (node (ref "R21") (pin "2") (pinfunction "2_2") (pintype "passive"))
      (node (ref "R22") (pin "1") (pinfunction "1_1") (pintype "passive"))
      (node (ref "R26") (pin "2") (pinfunction "2_2") (pintype "passive"))
      (node (ref "R4") (pin "1") (pinfunction "1_1") (pintype "passive"))
      (node (ref "R42") (pin "2") (pinfunction "2_2") (pintype "passive"))
      (node (ref "R43") (pin "2") (pinfunction "2_2") (pintype "passive"))
      (node (ref "R46") (pin "1") (pinfunction "1_1") (pintype "passive"))
      (node (ref "R50") (pin "2") (pinfunction "2_2") (pintype "passive"))
      (node (ref "R51") (pin "2") (pinfunction "2_2") (pintype "passive"))
      (node (ref "R52") (pin "2") (pinfunction "2_2") (pintype "passive"))
      (node (ref "R54") (pin "2") (pinfunction "2_2") (pintype "passive"))
      (node (ref "R55") (pin "2") (pinfunction "2_2") (pintype "passive"))
      (node (ref "S1") (pin "2") (pinfunction "2_2") (pintype "passive"))
      (node (ref "U1") (pin "2") (pinfunction "GND_2") (pintype "passive"))
      (node (ref "U2") (pin "4") (pinfunction "GND_4") (pintype "power_in"))
      (node (ref "U2") (pin "8") (pinfunction "GND2_8") (pintype "passive"))
      (node (ref "U3") (pin "12") (pinfunction "VSSA_12") (pintype "power_in"))
      (node (ref "U3") (pin "18") (pinfunction "VSS_4_18") (pintype "power_in"))
      (node (ref "U3") (pin "31") (pinfunction "VSS_1_31") (pintype "power_in"))
      (node (ref "U3") (pin "47") (pinfunction "VSS_2_47") (pintype "power_in"))
      (node (ref "U3") (pin "63") (pinfunction "VSS_3_63") (pintype "power_in"))
      (node (ref "U4") (pin "11") (pinfunction "5A_11") (pintype "input"))
      (node (ref "U4") (pin "13") (pinfunction "6A_13") (pintype "input"))
      (node (ref "U4") (pin "5") (pinfunction "3A_5") (pintype "input"))
      (node (ref "U4") (pin "7") (pinfunction "GND_7") (pintype "power_in"))
      (node (ref "U4") (pin "9") (pinfunction "4A_9") (pintype "input"))
      (node (ref "U5") (pin "7") (pinfunction "GND_7") (pintype "power_in"))
      (node (ref "U6") (pin "2") (pintype "passive"))
    )
    (net (code "66") (name "Net-(D1-K)") (class "Default")
      (node (ref "C5") (pin "2") (pinfunction "2_2") (pintype "passive"))
      (node (ref "D1") (pin "2") (pinfunction "K_2") (pintype "passive"))
      (node (ref "U1") (pin "1") (pinfunction "VIN_1") (pintype "passive"))
      (node (ref "U1") (pin "3") (pinfunction "CE_3") (pintype "passive"))
    )
    (net (code "67") (name "Net-(J1-Pad1)") (class "Default")
      (node (ref "J1") (pin "1") (pinfunction "1_1") (pintype "passive"))
      (node (ref "J6") (pin "2") (pinfunction "2_2") (pintype "passive"))
    )
    (net (code "68") (name "Net-(J7-Pad2)") (class "Default")
      (node (ref "J7") (pin "2") (pinfunction "2_2") (pintype "passive"))
      (node (ref "S2") (pin "1") (pinfunction "1_1") (pintype "passive"))
    )
    (net (code "69") (name "Net-(J11-5V)") (class "Default")
      (node (ref "J11") (pin "1") (pinfunction "5V_1") (pintype "power_in"))
      (node (ref "S2") (pin "3") (pinfunction "3_3") (pintype "passive"))
    )
    (net (code "70") (name "Net-(L1-A)") (class "Default")
      (node (ref "L1") (pin "1") (pinfunction "A_1") (pintype "passive"))
      (node (ref "R1") (pin "1") (pinfunction "1_1") (pintype "passive"))
    )
    (net (code "71") (name "Net-(LED1-Pad2)") (class "Default")
      (node (ref "LED1") (pin "2") (pinfunction "2_2") (pintype "passive"))
      (node (ref "R51") (pin "1") (pinfunction "1_1") (pintype "passive"))
    )
    (net (code "72") (name "Net-(LED2-Pad2)") (class "Default")
      (node (ref "LED2") (pin "2") (pinfunction "2_2") (pintype "passive"))
      (node (ref "R52") (pin "1") (pinfunction "1_1") (pintype "passive"))
    )
    (net (code "73") (name "Net-(P8-Pad2)") (class "Default")
      (node (ref "P8") (pin "2") (pinfunction "2_2") (pintype "passive"))
      (node (ref "R3") (pin "1") (pinfunction "1_1") (pintype "passive"))
    )
    (net (code "74") (name "Net-(P9-Pad2)") (class "Default")
      (node (ref "P9") (pin "2") (pinfunction "2_2") (pintype "passive"))
      (node (ref "R30") (pin "1") (pinfunction "1_1") (pintype "passive"))
    )
    (net (code "75") (name "Net-(Q1-NG1)") (class "Default")
      (node (ref "Q1") (pin "2") (pinfunction "NG1_2") (pintype "passive"))
      (node (ref "R12") (pin "1") (pinfunction "1_1") (pintype "passive"))
      (node (ref "R23") (pin "1") (pinfunction "1_1") (pintype "passive"))
    )
    (net (code "76") (name "Net-(Q1-PG2)") (class "Default")
      (node (ref "Q1") (pin "4") (pinfunction "PG2_4") (pintype "passive"))
      (node (ref "Q3") (pin "3") (pinfunction "C_3") (pintype "passive"))
      (node (ref "R5") (pin "1") (pinfunction "1_1") (pintype "passive"))
    )
    (net (code "77") (name "Net-(Q2-NG1)") (class "Default")
      (node (ref "Q2") (pin "2") (pinfunction "NG1_2") (pintype "passive"))
      (node (ref "R10") (pin "1") (pinfunction "1_1") (pintype "passive"))
      (node (ref "R24") (pin "1") (pinfunction "1_1") (pintype "passive"))
    )
    (net (code "78") (name "Net-(Q2-PG2)") (class "Default")
      (node (ref "Q2") (pin "4") (pinfunction "PG2_4") (pintype "passive"))
      (node (ref "Q4") (pin "3") (pinfunction "C_3") (pintype "passive"))
      (node (ref "R6") (pin "1") (pinfunction "1_1") (pintype "passive"))
    )
    (net (code "79") (name "Net-(Q3-B)") (class "Default")
      (node (ref "Q3") (pin "1") (pinfunction "B_1") (pintype "passive"))
      (node (ref "R17") (pin "1") (pinfunction "1_1") (pintype "passive"))
      (node (ref "R22") (pin "2") (pinfunction "2_2") (pintype "passive"))
    )
    (net (code "80") (name "Net-(Q4-B)") (class "Default")
      (node (ref "Q4") (pin "1") (pinfunction "B_1") (pintype "passive"))
      (node (ref "R14") (pin "2") (pinfunction "2_2") (pintype "passive"))
      (node (ref "R26") (pin "1") (pinfunction "1_1") (pintype "passive"))
    )
    (net (code "81") (name "Net-(Q5-NG1)") (class "Default")
      (node (ref "Q5") (pin "2") (pinfunction "NG1_2") (pintype "passive"))
      (node (ref "R43") (pin "1") (pinfunction "1_1") (pintype "passive"))
      (node (ref "R47") (pin "1") (pinfunction "1_1") (pintype "passive"))
    )
    (net (code "82") (name "Net-(Q5-PG2)") (class "Default")
      (node (ref "Q5") (pin "4") (pinfunction "PG2_4") (pintype "passive"))
      (node (ref "Q7") (pin "3") (pinfunction "C_3") (pintype "passive"))
      (node (ref "R35") (pin "1") (pinfunction "1_1") (pintype "passive"))
    )
    (net (code "83") (name "Net-(Q6-NG1)") (class "Default")
      (node (ref "Q6") (pin "2") (pinfunction "NG1_2") (pintype "passive"))
      (node (ref "R42") (pin "1") (pinfunction "1_1") (pintype "passive"))
      (node (ref "R48") (pin "1") (pinfunction "1_1") (pintype "passive"))
    )
    (net (code "84") (name "Net-(Q6-PG2)") (class "Default")
      (node (ref "Q6") (pin "4") (pinfunction "PG2_4") (pintype "passive"))
      (node (ref "Q8") (pin "3") (pinfunction "C_3") (pintype "passive"))
      (node (ref "R36") (pin "1") (pinfunction "1_1") (pintype "passive"))
    )
    (net (code "85") (name "Net-(Q7-B)") (class "Default")
      (node (ref "Q7") (pin "1") (pinfunction "B_1") (pintype "passive"))
      (node (ref "R45") (pin "1") (pinfunction "1_1") (pintype "passive"))
      (node (ref "R46") (pin "2") (pinfunction "2_2") (pintype "passive"))
    )
    (net (code "86") (name "Net-(Q8-B)") (class "Default")
      (node (ref "Q8") (pin "1") (pinfunction "B_1") (pintype "passive"))
      (node (ref "R44") (pin "2") (pinfunction "2_2") (pintype "passive"))
      (node (ref "R50") (pin "1") (pinfunction "1_1") (pintype "passive"))
    )
    (net (code "87") (name "Net-(U3-OSC_IN{slash}PD0)") (class "Default")
      (node (ref "C16") (pin "2") (pinfunction "2_2") (pintype "passive"))
      (node (ref "U3") (pin "5") (pinfunction "OSC_IN/PD0_5") (pintype "input"))
      (node (ref "X1") (pin "2") (pinfunction "2_2") (pintype "passive"))
    )
    (net (code "88") (name "Net-(U3-OSC_OUT{slash}PD1)") (class "Default")
      (node (ref "C17") (pin "2") (pinfunction "2_2") (pintype "passive"))
      (node (ref "U3") (pin "6") (pinfunction "OSC_OUT/PD1_6") (pintype "output"))
      (node (ref "X1") (pin "1") (pinfunction "1_1") (pintype "passive"))
    )
    (net (code "89") (name "Net-(U3-VBAT)") (class "Default")
      (node (ref "R40") (pin "2") (pinfunction "2_2") (pintype "passive"))
      (node (ref "U3") (pin "1") (pinfunction "VBAT_1") (pintype "power_in"))
    )
    (net (code "90") (name "VCC-3.3V") (class "Default")
      (node (ref "C1") (pin "1") (pinfunction "1_1") (pintype "passive"))
      (node (ref "C18") (pin "2") (pinfunction "2_2") (pintype "passive"))
      (node (ref "C19") (pin "2") (pinfunction "2_2") (pintype "passive"))
      (node (ref "C2") (pin "1") (pinfunction "1_1") (pintype "passive"))
      (node (ref "C20") (pin "2") (pinfunction "2_2") (pintype "passive"))
      (node (ref "C24") (pin "1") (pinfunction "1_1") (pintype "passive"))
      (node (ref "C26") (pin "1") (pinfunction "1_1") (pintype "passive"))
      (node (ref "C3") (pin "2") (pinfunction "2_2") (pintype "passive"))
      (node (ref "C4") (pin "1") (pinfunction "1_1") (pintype "passive"))
      (node (ref "C6") (pin "1") (pinfunction "1_1") (pintype "passive"))
      (node (ref "C7") (pin "1") (pinfunction "1_1") (pintype "passive"))
      (node (ref "C8") (pin "1") (pinfunction "1_1") (pintype "passive"))
      (node (ref "J2") (pin "2") (pinfunction "2_2") (pintype "passive"))
      (node (ref "J3") (pin "1") (pinfunction "1_1") (pintype "passive"))
      (node (ref "J4") (pin "2") (pinfunction "2_2") (pintype "passive"))
      (node (ref "J5") (pin "1") (pinfunction "1_1") (pintype "passive"))
      (node (ref "J8") (pin "7") (pinfunction "7_7") (pintype "passive"))
      (node (ref "P10") (pin "4") (pinfunction "4_4") (pintype "passive"))
      (node (ref "P2") (pin "10") (pinfunction "10_10") (pintype "passive"))
      (node (ref "P2") (pin "12") (pinfunction "12_12") (pintype "passive"))
      (node (ref "P2") (pin "2") (pinfunction "2_2") (pintype "passive"))
      (node (ref "P2") (pin "4") (pinfunction "4_4") (pintype "passive"))
      (node (ref "P2") (pin "6") (pinfunction "6_6") (pintype "passive"))
      (node (ref "P2") (pin "8") (pinfunction "8_8") (pintype "passive"))
      (node (ref "R1") (pin "2") (pinfunction "2_2") (pintype "passive"))
      (node (ref "R11") (pin "1") (pinfunction "1_1") (pintype "passive"))
      (node (ref "R13") (pin "2") (pinfunction "2_2") (pintype "passive"))
      (node (ref "R15") (pin "1") (pinfunction "1_1") (pintype "passive"))
      (node (ref "R16") (pin "2") (pinfunction "2_2") (pintype "passive"))
      (node (ref "R18") (pin "1") (pinfunction "1_1") (pintype "passive"))
      (node (ref "R19") (pin "2") (pinfunction "2_2") (pintype "passive"))
      (node (ref "R2") (pin "2") (pinfunction "2_2") (pintype "passive"))
      (node (ref "R20") (pin "2") (pinfunction "2_2") (pintype "passive"))
      (node (ref "R27") (pin "2") (pinfunction "2_2") (pintype "passive"))
      (node (ref "R28") (pin "2") (pinfunction "2_2") (pintype "passive"))
      (node (ref "R29") (pin "1") (pinfunction "1_1") (pintype "passive"))
      (node (ref "R3") (pin "2") (pinfunction "2_2") (pintype "passive"))
      (node (ref "R30") (pin "2") (pinfunction "2_2") (pintype "passive"))
      (node (ref "R31") (pin "1") (pinfunction "1_1") (pintype "passive"))
      (node (ref "R32") (pin "2") (pinfunction "2_2") (pintype "passive"))
      (node (ref "R33") (pin "2") (pinfunction "2_2") (pintype "passive"))
      (node (ref "R34") (pin "2") (pinfunction "2_2") (pintype "passive"))
      (node (ref "R37") (pin "2") (pinfunction "2_2") (pintype "passive"))
      (node (ref "R38") (pin "2") (pinfunction "2_2") (pintype "passive"))
      (node (ref "R39") (pin "2") (pinfunction "2_2") (pintype "passive"))
      (node (ref "R40") (pin "1") (pinfunction "1_1") (pintype "passive"))
      (node (ref "R41") (pin "2") (pinfunction "2_2") (pintype "passive"))
      (node (ref "R53") (pin "1") (pinfunction "1_1") (pintype "passive"))
      (node (ref "R7") (pin "1") (pinfunction "1_1") (pintype "passive"))
      (node (ref "R8") (pin "1") (pinfunction "1_1") (pintype "passive"))
      (node (ref "R9") (pin "1") (pinfunction "1_1") (pintype "passive"))
      (node (ref "U1") (pin "5") (pinfunction "OUT_5") (pintype "passive"))
      (node (ref "U2") (pin "1") (pinfunction "VCC_1") (pintype "power_in"))
      (node (ref "U3") (pin "13") (pinfunction "VDDA_13") (pintype "power_in"))
      (node (ref "U3") (pin "19") (pinfunction "VDD_4_19") (pintype "power_in"))
      (node (ref "U3") (pin "32") (pinfunction "VDD_1_32") (pintype "power_in"))
      (node (ref "U3") (pin "48") (pinfunction "VDD_2_48") (pintype "power_in"))
      (node (ref "U3") (pin "64") (pinfunction "VDD_3_64") (pintype "power_in"))
    )
    (net (code "91") (name "VCC-5V") (class "Default")
      (node (ref "C10") (pin "1") (pinfunction "1_1") (pintype "passive"))
      (node (ref "C22") (pin "2") (pinfunction "2_2") (pintype "passive"))
      (node (ref "C23") (pin "1") (pinfunction "1_1") (pintype "passive"))
      (node (ref "C25") (pin "1") (pinfunction "1_1") (pintype "passive"))
      (node (ref "D1") (pin "1") (pinfunction "A_1") (pintype "passive"))
      (node (ref "J10") (pin "1") (pinfunction "1-P_1") (pintype "passive"))
      (node (ref "J6") (pin "1") (pinfunction "1_1") (pintype "passive"))
      (node (ref "J9") (pin "2") (pinfunction "2_2") (pintype "passive"))
      (node (ref "P1") (pin "10") (pinfunction "10_10") (pintype "passive"))
      (node (ref "P1") (pin "12") (pinfunction "12_12") (pintype "passive"))
      (node (ref "P1") (pin "2") (pinfunction "2_2") (pintype "passive"))
      (node (ref "P1") (pin "4") (pinfunction "4_4") (pintype "passive"))
      (node (ref "P1") (pin "6") (pinfunction "6_6") (pintype "passive"))
      (node (ref "P1") (pin "8") (pinfunction "8_8") (pintype "passive"))
      (node (ref "P12") (pin "2") (pinfunction "2_2") (pintype "passive"))
      (node (ref "P4") (pin "2") (pinfunction "2_2") (pintype "passive"))
      (node (ref "P5") (pin "2") (pinfunction "2_2") (pintype "passive"))
      (node (ref "P6") (pin "2") (pinfunction "2_2") (pintype "passive"))
      (node (ref "P7") (pin "2") (pinfunction "2_2") (pintype "passive"))
      (node (ref "U4") (pin "14") (pinfunction "VCC_14") (pintype "power_in"))
      (node (ref "U5") (pin "14") (pinfunction "VCC_14") (pintype "power_in"))
      (node (ref "U6") (pin "3") (pinfunction "OUT_3") (pintype "passive"))
    )
    (net (code "92") (name "VCC-IN") (class "Default")
      (node (ref "C12") (pin "1") (pinfunction "1_1") (pintype "passive"))
      (node (ref "P11") (pin "1") (pinfunction "1_1") (pintype "passive"))
      (node (ref "P12") (pin "1") (pinfunction "1_1") (pintype "passive"))
      (node (ref "Q1") (pin "3") (pinfunction "PS2_3") (pintype "passive"))
      (node (ref "Q2") (pin "3") (pinfunction "PS2_3") (pintype "passive"))
      (node (ref "Q5") (pin "3") (pinfunction "PS2_3") (pintype "passive"))
      (node (ref "Q6") (pin "3") (pinfunction "PS2_3") (pintype "passive"))
      (node (ref "R35") (pin "2") (pinfunction "2_2") (pintype "passive"))
      (node (ref "R36") (pin "2") (pinfunction "2_2") (pintype "passive"))
      (node (ref "R4") (pin "2") (pinfunction "2_2") (pintype "passive"))
      (node (ref "R5") (pin "2") (pinfunction "2_2") (pintype "passive"))
      (node (ref "R6") (pin "2") (pinfunction "2_2") (pintype "passive"))
      (node (ref "S2") (pin "2") (pinfunction "2_2") (pintype "passive"))
    )
    (net (code "93") (name "unconnected-(J10-2-D--Pad2)") (class "Default")
      (node (ref "J10") (pin "2") (pinfunction "2-D-_2") (pintype "passive+no_connect"))
    )
    (net (code "94") (name "unconnected-(J10-3-D+-Pad3)") (class "Default")
      (node (ref "J10") (pin "3") (pinfunction "3-D+_3") (pintype "passive+no_connect"))
    )
    (net (code "95") (name "unconnected-(J10-Pad0)") (class "Default")
      (node (ref "J10") (pin "0") (pinfunction "0_0") (pintype "passive"))
    )
    (net (code "96") (name "unconnected-(J11-D+-Pad3)") (class "Default")
      (node (ref "J11") (pin "3") (pinfunction "D+_3") (pintype "passive+no_connect"))
    )
    (net (code "97") (name "unconnected-(J11-D--Pad2)") (class "Default")
      (node (ref "J11") (pin "2") (pinfunction "D-_2") (pintype "passive+no_connect"))
    )
    (net (code "98") (name "unconnected-(J11-NAN-Pad4)") (class "Default")
      (node (ref "J11") (pin "4") (pinfunction "NAN_4") (pintype "passive+no_connect"))
    )
    (net (code "99") (name "unconnected-(U1-NC-Pad4)") (class "Default")
      (node (ref "U1") (pin "4") (pinfunction "NC_4") (pintype "passive"))
    )
    (net (code "100") (name "unconnected-(U2-SCL-Pad6)") (class "Default")
      (node (ref "U2") (pin "6") (pinfunction "SCL_6") (pintype "input+no_connect"))
    )
    (net (code "101") (name "unconnected-(U2-SDA-Pad7)") (class "Default")
      (node (ref "U2") (pin "7") (pinfunction "SDA_7") (pintype "bidirectional+no_connect"))
    )
    (net (code "102") (name "unconnected-(U2-VCC-Pad5)") (class "Default")
      (node (ref "U2") (pin "5") (pinfunction "VCC_5") (pintype "power_in+no_connect"))
    )
    (net (code "103") (name "unconnected-(U4-3Y-Pad6)") (class "Default")
      (node (ref "U4") (pin "6") (pinfunction "3Y_6") (pintype "output"))
    )
    (net (code "104") (name "unconnected-(U4-4Y-Pad8)") (class "Default")
      (node (ref "U4") (pin "8") (pinfunction "4Y_8") (pintype "output"))
    )
    (net (code "105") (name "unconnected-(U4-5Y-Pad10)") (class "Default")
      (node (ref "U4") (pin "10") (pinfunction "5Y_10") (pintype "output"))
    )
    (net (code "106") (name "unconnected-(U4-6Y-Pad12)") (class "Default")
      (node (ref "U4") (pin "12") (pinfunction "6Y_12") (pintype "output"))
    )
    (net (code "107") (name "unconnected-(V1-Pad0)") (class "Default")
      (node (ref "V1") (pin "0") (pinfunction "0_0") (pintype "passive"))
    )
    (net (code "108") (name "unconnected-(V2-Pad0)") (class "Default")
      (node (ref "V2") (pin "0") (pinfunction "0_0") (pintype "passive"))
    )
    (net (code "109") (name "unconnected-(V3-Pad0)") (class "Default")
      (node (ref "V3") (pin "0") (pinfunction "0_0") (pintype "passive"))
    )
    (net (code "110") (name "unconnected-(V4-Pad0)") (class "Default")
      (node (ref "V4") (pin "0") (pinfunction "0_0") (pintype "passive"))
    )
  )
)
